# LEDSEQUENCER.net
KiCad netlist of a schematic drawn in Altium Designer
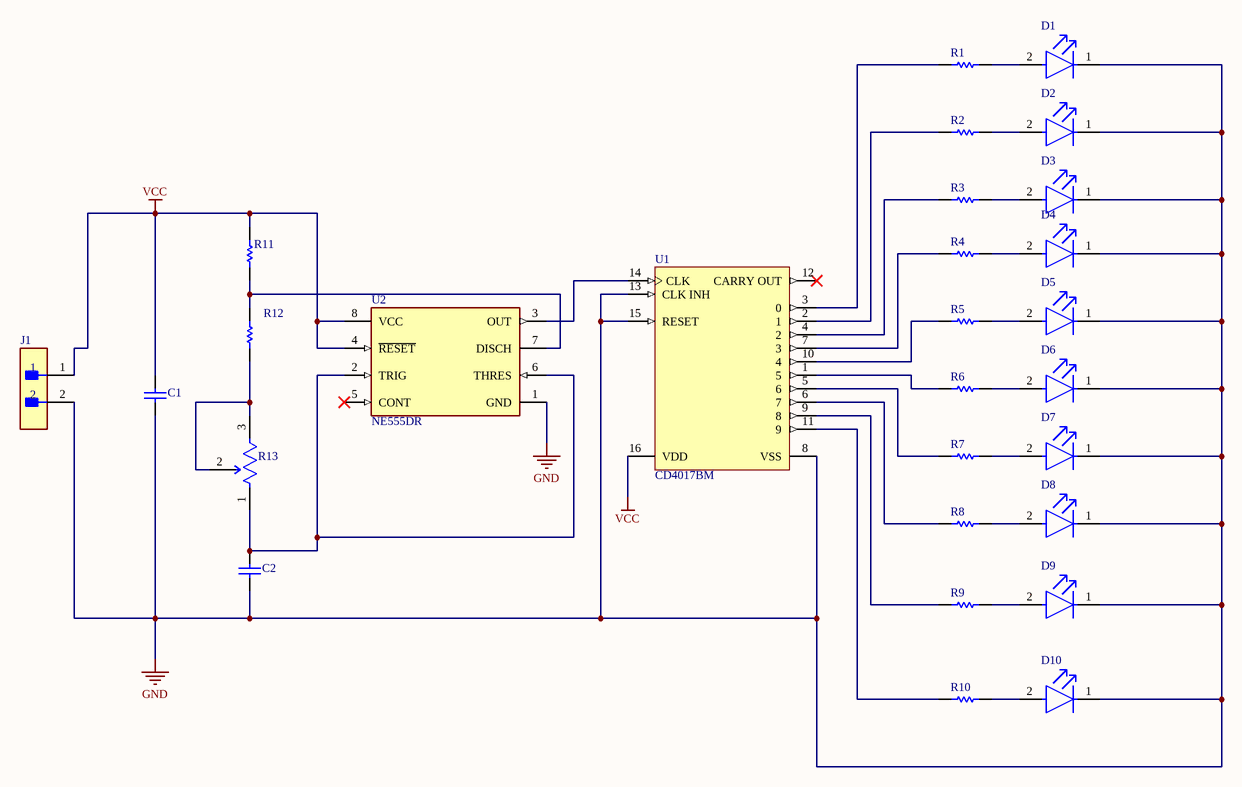
[diagram p0: LEDSEQUENCER.SchDoc]

(export (version "E")
  (design (tool "Eeschema 10.0.6"))
  (components
    (comp (ref "C1")
      (value "1uf")
      (footprint "CAPC2013X135X45LL10T25")
      (fields (field (name "MANUFACTURER") "Murata") (field (name "PART NUMBER") "GRM21BR71H105KA12L"))
      (libsource (lib "Altium Content Vault") (part "CAP"))
    )
    (comp (ref "C2")
      (value "1uf")
      (footprint "CAPC2013X135X45LL10T25")
      (fields (field (name "MANUFACTURER") "Murata") (field (name "PART NUMBER") "GRM21BR71H105KA12L"))
      (libsource (lib "Altium Content Vault") (part "CAP"))
    )
    (comp (ref "D1")
      (value "HLMP-1301")
      (footprint "FP-HLMP-1301-MFG")
      (description "LED RED DIFFUSED T-1 T/H")
      (fields
        (field (name "OCTOPART") "https://octopart.com/hlmp-1301-broadcom-71130345")
        (field (name "MANUFACTURER") "Broadcom")
      )
      (libsource (lib "Altium Content Vault") (part "8706943c75ba83719d021d2fdc84c58"))
    )
    (comp (ref "D2")
      (value "HLMP-1301")
      (footprint "FP-HLMP-1301-MFG")
      (description "LED RED DIFFUSED T-1 T/H")
      (fields
        (field (name "OCTOPART") "https://octopart.com/hlmp-1301-broadcom-71130345")
        (field (name "MANUFACTURER") "Broadcom")
      )
      (libsource (lib "Altium Content Vault") (part "8706943c75ba83719d021d2fdc84c58"))
    )
    (comp (ref "D3")
      (value "HLMP-1301")
      (footprint "FP-HLMP-1301-MFG")
      (description "LED RED DIFFUSED T-1 T/H")
      (fields
        (field (name "OCTOPART") "https://octopart.com/hlmp-1301-broadcom-71130345")
        (field (name "MANUFACTURER") "Broadcom")
      )
      (libsource (lib "Altium Content Vault") (part "8706943c75ba83719d021d2fdc84c58"))
    )
    (comp (ref "D4")
      (value "HLMP-1301")
      (footprint "FP-HLMP-1301-MFG")
      (description "LED RED DIFFUSED T-1 T/H")
      (fields
        (field (name "OCTOPART") "https://octopart.com/hlmp-1301-broadcom-71130345")
        (field (name "MANUFACTURER") "Broadcom")
      )
      (libsource (lib "Altium Content Vault") (part "8706943c75ba83719d021d2fdc84c58"))
    )
    (comp (ref "D5")
      (value "HLMP-1301")
      (footprint "FP-HLMP-1301-MFG")
      (description "LED RED DIFFUSED T-1 T/H")
      (fields
        (field (name "OCTOPART") "https://octopart.com/hlmp-1301-broadcom-71130345")
        (field (name "MANUFACTURER") "Broadcom")
      )
      (libsource (lib "Altium Content Vault") (part "8706943c75ba83719d021d2fdc84c58"))
    )
    (comp (ref "D6")
      (value "HLMP-1301")
      (footprint "FP-HLMP-1301-MFG")
      (description "LED RED DIFFUSED T-1 T/H")
      (fields
        (field (name "OCTOPART") "https://octopart.com/hlmp-1301-broadcom-71130345")
        (field (name "MANUFACTURER") "Broadcom")
      )
      (libsource (lib "Altium Content Vault") (part "8706943c75ba83719d021d2fdc84c58"))
    )
    (comp (ref "D7")
      (value "HLMP-1301")
      (footprint "FP-HLMP-1301-MFG")
      (description "LED RED DIFFUSED T-1 T/H")
      (fields
        (field (name "OCTOPART") "https://octopart.com/hlmp-1301-broadcom-71130345")
        (field (name "MANUFACTURER") "Broadcom")
      )
      (libsource (lib "Altium Content Vault") (part "8706943c75ba83719d021d2fdc84c58"))
    )
    (comp (ref "D8")
      (value "HLMP-1301")
      (footprint "FP-HLMP-1301-MFG")
      (description "LED RED DIFFUSED T-1 T/H")
      (fields
        (field (name "OCTOPART") "https://octopart.com/hlmp-1301-broadcom-71130345")
        (field (name "MANUFACTURER") "Broadcom")
      )
      (libsource (lib "Altium Content Vault") (part "8706943c75ba83719d021d2fdc84c58"))
    )
    (comp (ref "D9")
      (value "HLMP-1301")
      (footprint "FP-HLMP-1301-MFG")
      (description "LED RED DIFFUSED T-1 T/H")
      (fields
        (field (name "OCTOPART") "https://octopart.com/hlmp-1301-broadcom-71130345")
        (field (name "MANUFACTURER") "Broadcom")
      )
      (libsource (lib "Altium Content Vault") (part "8706943c75ba83719d021d2fdc84c58"))
    )
    (comp (ref "D10")
      (value "HLMP-1301")
      (footprint "FP-HLMP-1301-MFG")
      (description "LED RED DIFFUSED T-1 T/H")
      (fields
        (field (name "OCTOPART") "https://octopart.com/hlmp-1301-broadcom-71130345")
        (field (name "MANUFACTURER") "Broadcom")
      )
      (libsource (lib "Altium Content Vault") (part "8706943c75ba83719d021d2fdc84c58"))
    )
    (comp (ref "J1")
      (value "M20-9990246")
      (footprint "FP-M20-9990246-MFG")
      (description "Connector Header Through Hole 2 position 0.100\" (2.54mm)")
      (fields (field (name "OCTOPART") "https://octopart.com/m20-9990246-harwin-2590635"))
      (libsource (lib "Altium Content Vault") (part "3bc925449376181038e59eaffc5286c"))
    )
    (comp (ref "R1")
      (value "1k")
      (footprint "RESC2013X60X35ML10T20")
      (description "Chip Resistor, 1 KOhm, +/- 1%, 125 mW, -55 to 155 degC, 0805 (2012 Metric), RoHS, Tape and Reel")
      (fields (field (name "TOLERANCE") "1%") (field (name "MANUFACTURER") "Yageo"))
      (libsource (lib "Altium Content Vault") (part "RES-2"))
    )
    (comp (ref "R2")
      (value "RC0805FR-071KL")
      (footprint "RESC2013X60X35ML10T20")
      (description "Chip Resistor, 1 KOhm, +/- 1%, 125 mW, -55 to 155 degC, 0805 (2012 Metric), RoHS, Tape and Reel")
      (fields (field (name "TOLERANCE") "1%") (field (name "MANUFACTURER") "Yageo"))
      (libsource (lib "Altium Content Vault") (part "RES-2"))
    )
    (comp (ref "R3")
      (value "RC0805FR-071KL")
      (footprint "RESC2013X60X35ML10T20")
      (description "Chip Resistor, 1 KOhm, +/- 1%, 125 mW, -55 to 155 degC, 0805 (2012 Metric), RoHS, Tape and Reel")
      (fields (field (name "TOLERANCE") "1%") (field (name "MANUFACTURER") "Yageo"))
      (libsource (lib "Altium Content Vault") (part "RES-2"))
    )
    (comp (ref "R4")
      (value "RC0805FR-071KL")
      (footprint "RESC2013X60X35ML10T20")
      (description "Chip Resistor, 1 KOhm, +/- 1%, 125 mW, -55 to 155 degC, 0805 (2012 Metric), RoHS, Tape and Reel")
      (fields (field (name "TOLERANCE") "1%") (field (name "MANUFACTURER") "Yageo"))
      (libsource (lib "Altium Content Vault") (part "RES-2"))
    )
    (comp (ref "R5")
      (value "RC0805FR-071KL")
      (footprint "RESC2013X60X35ML10T20")
      (description "Chip Resistor, 1 KOhm, +/- 1%, 125 mW, -55 to 155 degC, 0805 (2012 Metric), RoHS, Tape and Reel")
      (fields (field (name "TOLERANCE") "1%") (field (name "MANUFACTURER") "Yageo"))
      (libsource (lib "Altium Content Vault") (part "RES-2"))
    )
    (comp (ref "R6")
      (value "RC0805FR-071KL")
      (footprint "RESC2013X60X35ML10T20")
      (description "Chip Resistor, 1 KOhm, +/- 1%, 125 mW, -55 to 155 degC, 0805 (2012 Metric), RoHS, Tape and Reel")
      (fields (field (name "TOLERANCE") "1%") (field (name "MANUFACTURER") "Yageo"))
      (libsource (lib "Altium Content Vault") (part "RES-2"))
    )
    (comp (ref "R7")
      (value "RC0805FR-071KL")
      (footprint "RESC2013X60X35ML10T20")
      (description "Chip Resistor, 1 KOhm, +/- 1%, 125 mW, -55 to 155 degC, 0805 (2012 Metric), RoHS, Tape and Reel")
      (fields (field (name "TOLERANCE") "1%") (field (name "MANUFACTURER") "Yageo"))
      (libsource (lib "Altium Content Vault") (part "RES-2"))
    )
    (comp (ref "R8")
      (value "RC0805FR-071KL")
      (footprint "RESC2013X60X35ML10T20")
      (description "Chip Resistor, 1 KOhm, +/- 1%, 125 mW, -55 to 155 degC, 0805 (2012 Metric), RoHS, Tape and Reel")
      (fields (field (name "TOLERANCE") "1%") (field (name "MANUFACTURER") "Yageo"))
      (libsource (lib "Altium Content Vault") (part "RES-2"))
    )
    (comp (ref "R9")
      (value "RC0805FR-071KL")
      (footprint "RESC2013X60X35ML10T20")
      (description "Chip Resistor, 1 KOhm, +/- 1%, 125 mW, -55 to 155 degC, 0805 (2012 Metric), RoHS, Tape and Reel")
      (fields (field (name "TOLERANCE") "1%") (field (name "MANUFACTURER") "Yageo"))
      (libsource (lib "Altium Content Vault") (part "RES-2"))
    )
    (comp (ref "R10")
      (value "RC0805FR-071KL")
      (footprint "RESC2013X60X35ML10T20")
      (description "Chip Resistor, 1 KOhm, +/- 1%, 125 mW, -55 to 155 degC, 0805 (2012 Metric), RoHS, Tape and Reel")
      (fields (field (name "TOLERANCE") "1%") (field (name "MANUFACTURER") "Yageo"))
      (libsource (lib "Altium Content Vault") (part "RES-2"))
    )
    (comp (ref "R11")
      (value "2.2k")
      (footprint "RESC2013X60X35ML10T20")
      (description "Chip Resistor, 1 KOhm, +/- 1%, 125 mW, -55 to 155 degC, 0805 (2012 Metric), RoHS, Tape and Reel")
      (fields (field (name "TOLERANCE") "1%") (field (name "MANUFACTURER") "Yageo"))
      (libsource (lib "Altium Content Vault") (part "RES-2"))
    )
    (comp (ref "R12")
      (value "10k")
      (footprint "RESC2013X60X35ML10T20")
      (description "Chip Resistor, 1 KOhm, +/- 1%, 125 mW, -55 to 155 degC, 0805 (2012 Metric), RoHS, Tape and Reel")
      (fields (field (name "TOLERANCE") "1%") (field (name "MANUFACTURER") "Yageo"))
      (libsource (lib "Altium Content Vault") (part "RES-2"))
    )
    (comp (ref "R13")
      (value "50k")
      (footprint "FP-3386P-MFG")
      (description "TRIMMER 100K OHM 0.5W PC PIN TOP")
      (fields (field (name "TOLERANCE") "10%"))
      (libsource (lib "Altium Content Vault") (part "13357d81287629c2fd191d242cfa50c"))
    )
    (comp (ref "U1")
      (value "CD4017BM")
      (footprint "D0016A_N")
      (description "CMOS Decade Counter with 10 Decoded Outputs, D0016A, TUBE")
      (fields
        (field (name "GENERIC PART NUMBER") "CD4017B")
        (field (name "MANUFACTURER") "Texas Instruments")
      )
      (libsource (lib "Altium Content Vault") (part "TI-CD4017B-16"))
    )
    (comp (ref "U2")
      (value "NE555DR")
      (footprint "FP-D0008A-IPC_A")
      (description "IC OSC SGL TIMER 100KHZ 8-SOIC")
      (libsource (lib "Altium Content Vault") (part "a29bba90211dec1890110b94dad7d53"))
    )
  )
  (nets
    (net (code "1") (name "GND") (class "Default")
      (node (ref "C1") (pin "1") (pinfunction "1_1") (pintype "passive"))
      (node (ref "C2") (pin "1") (pinfunction "1_1") (pintype "passive"))
      (node (ref "D1") (pin "1") (pinfunction "C_1") (pintype "passive"))
      (node (ref "D10") (pin "1") (pinfunction "C_1") (pintype "passive"))
      (node (ref "D2") (pin "1") (pinfunction "C_1") (pintype "passive"))
      (node (ref "D3") (pin "1") (pinfunction "C_1") (pintype "passive"))
      (node (ref "D4") (pin "1") (pinfunction "C_1") (pintype "passive"))
      (node (ref "D5") (pin "1") (pinfunction "C_1") (pintype "passive"))
      (node (ref "D6") (pin "1") (pinfunction "C_1") (pintype "passive"))
      (node (ref "D7") (pin "1") (pinfunction "C_1") (pintype "passive"))
      (node (ref "D8") (pin "1") (pinfunction "C_1") (pintype "passive"))
      (node (ref "D9") (pin "1") (pinfunction "C_1") (pintype "passive"))
      (node (ref "J1") (pin "2") (pinfunction "2_2") (pintype "passive"))
      (node (ref "U1") (pin "13") (pinfunction "CLK_INH_13") (pintype "input"))
      (node (ref "U1") (pin "15") (pinfunction "RESET_15") (pintype "input"))
      (node (ref "U1") (pin "8") (pinfunction "VSS_8") (pintype "power_in"))
      (node (ref "U2") (pin "1") (pinfunction "GND_1") (pintype "power_in"))
    )
    (net (code "2") (name "Net-(D1-A)") (class "Default")
      (node (ref "D1") (pin "2") (pinfunction "A_2") (pintype "passive"))
      (node (ref "R1") (pin "2") (pinfunction "2_2") (pintype "passive"))
    )
    (net (code "3") (name "Net-(D2-A)") (class "Default")
      (node (ref "D2") (pin "2") (pinfunction "A_2") (pintype "passive"))
      (node (ref "R2") (pin "2") (pinfunction "2_2") (pintype "passive"))
    )
    (net (code "4") (name "Net-(D3-A)") (class "Default")
      (node (ref "D3") (pin "2") (pinfunction "A_2") (pintype "passive"))
      (node (ref "R3") (pin "2") (pinfunction "2_2") (pintype "passive"))
    )
    (net (code "5") (name "Net-(D4-A)") (class "Default")
      (node (ref "D4") (pin "2") (pinfunction "A_2") (pintype "passive"))
      (node (ref "R4") (pin "2") (pinfunction "2_2") (pintype "passive"))
    )
    (net (code "6") (name "Net-(D5-A)") (class "Default")
      (node (ref "D5") (pin "2") (pinfunction "A_2") (pintype "passive"))
      (node (ref "R5") (pin "2") (pinfunction "2_2") (pintype "passive"))
    )
    (net (code "7") (name "Net-(D6-A)") (class "Default")
      (node (ref "D6") (pin "2") (pinfunction "A_2") (pintype "passive"))
      (node (ref "R6") (pin "2") (pinfunction "2_2") (pintype "passive"))
    )
    (net (code "8") (name "Net-(D7-A)") (class "Default")
      (node (ref "D7") (pin "2") (pinfunction "A_2") (pintype "passive"))
      (node (ref "R7") (pin "2") (pinfunction "2_2") (pintype "passive"))
    )
    (net (code "9") (name "Net-(D8-A)") (class "Default")
      (node (ref "D8") (pin "2") (pinfunction "A_2") (pintype "passive"))
      (node (ref "R8") (pin "2") (pinfunction "2_2") (pintype "passive"))
    )
    (net (code "10") (name "Net-(D9-A)") (class "Default")
      (node (ref "D9") (pin "2") (pinfunction "A_2") (pintype "passive"))
      (node (ref "R9") (pin "2") (pinfunction "2_2") (pintype "passive"))
    )
    (net (code "11") (name "Net-(D10-A)") (class "Default")
      (node (ref "D10") (pin "2") (pinfunction "A_2") (pintype "passive"))
      (node (ref "R10") (pin "2") (pinfunction "2_2") (pintype "passive"))
    )
    (net (code "12") (name "Net-(R13-CCW)") (class "Default")
      (node (ref "C2") (pin "2") (pinfunction "2_2") (pintype "passive"))
      (node (ref "R13") (pin "1") (pinfunction "CCW_1") (pintype "passive"))
      (node (ref "U2") (pin "2") (pinfunction "TRIG_2") (pintype "input"))
      (node (ref "U2") (pin "6") (pinfunction "THRES_6") (pintype "input"))
    )
    (net (code "13") (name "Net-(R13-CW)") (class "Default")
      (node (ref "R12") (pin "1") (pinfunction "1_1") (pintype "passive"))
      (node (ref "R13") (pin "2") (pinfunction "WIPER_2") (pintype "passive"))
      (node (ref "R13") (pin "3") (pinfunction "CW_3") (pintype "passive"))
    )
    (net (code "14") (name "Net-(U1-0)") (class "Default")
      (node (ref "R1") (pin "1") (pinfunction "1_1") (pintype "passive"))
      (node (ref "U1") (pin "3") (pinfunction "0_3") (pintype "output"))
    )
    (net (code "15") (name "Net-(U1-1)") (class "Default")
      (node (ref "R2") (pin "1") (pinfunction "1_1") (pintype "passive"))
      (node (ref "U1") (pin "2") (pinfunction "1_2") (pintype "output"))
    )
    (net (code "16") (name "Net-(U1-2)") (class "Default")
      (node (ref "R3") (pin "1") (pinfunction "1_1") (pintype "passive"))
      (node (ref "U1") (pin "4") (pinfunction "2_4") (pintype "output"))
    )
    (net (code "17") (name "Net-(U1-3)") (class "Default")
      (node (ref "R4") (pin "1") (pinfunction "1_1") (pintype "passive"))
      (node (ref "U1") (pin "7") (pinfunction "3_7") (pintype "output"))
    )
    (net (code "18") (name "Net-(U1-4)") (class "Default")
      (node (ref "R5") (pin "1") (pinfunction "1_1") (pintype "passive"))
      (node (ref "U1") (pin "10") (pinfunction "4_10") (pintype "output"))
    )
    (net (code "19") (name "Net-(U1-5)") (class "Default")
      (node (ref "R6") (pin "1") (pinfunction "1_1") (pintype "passive"))
      (node (ref "U1") (pin "1") (pinfunction "5_1") (pintype "output"))
    )
    (net (code "20") (name "Net-(U1-6)") (class "Default")
      (node (ref "R7") (pin "1") (pinfunction "1_1") (pintype "passive"))
      (node (ref "U1") (pin "5") (pinfunction "6_5") (pintype "output"))
    )
    (net (code "21") (name "Net-(U1-7)") (class "Default")
      (node (ref "R8") (pin "1") (pinfunction "1_1") (pintype "passive"))
      (node (ref "U1") (pin "6") (pinfunction "7_6") (pintype "output"))
    )
    (net (code "22") (name "Net-(U1-8)") (class "Default")
      (node (ref "R9") (pin "1") (pinfunction "1_1") (pintype "passive"))
      (node (ref "U1") (pin "9") (pinfunction "8_9") (pintype "output"))
    )
    (net (code "23") (name "Net-(U1-9)") (class "Default")
      (node (ref "R10") (pin "1") (pinfunction "1_1") (pintype "passive"))
      (node (ref "U1") (pin "11") (pinfunction "9_11") (pintype "output"))
    )
    (net (code "24") (name "Net-(U1-CLK)") (class "Default")
      (node (ref "U1") (pin "14") (pinfunction "CLK_14") (pintype "input"))
      (node (ref "U2") (pin "3") (pinfunction "OUT_3") (pintype "output"))
    )
    (net (code "25") (name "Net-(U2-DISCH)") (class "Default")
      (node (ref "R11") (pin "1") (pinfunction "1_1") (pintype "passive"))
      (node (ref "R12") (pin "2") (pinfunction "2_2") (pintype "passive"))
      (node (ref "U2") (pin "7") (pinfunction "DISCH_7") (pintype "open_collector"))
    )
    (net (code "26") (name "VCC") (class "Default")
      (node (ref "C1") (pin "2") (pinfunction "2_2") (pintype "passive"))
      (node (ref "J1") (pin "1") (pinfunction "1_1") (pintype "passive"))
      (node (ref "R11") (pin "2") (pinfunction "2_2") (pintype "passive"))
      (node (ref "U1") (pin "16") (pinfunction "VDD_16") (pintype "power_in"))
      (node (ref "U2") (pin "4") (pinfunction "~{RESET}_4") (pintype "input"))
      (node (ref "U2") (pin "8") (pinfunction "VCC_8") (pintype "power_in"))
    )
    (net (code "27") (name "unconnected-(U1-CARRY_OUT-Pad12)") (class "Default")
      (node (ref "U1") (pin "12") (pinfunction "CARRY_OUT_12") (pintype "output+no_connect"))
    )
    (net (code "28") (name "unconnected-(U2-CONT-Pad5)") (class "Default")
      (node (ref "U2") (pin "5") (pinfunction "CONT_5") (pintype "input+no_connect"))
    )
  )
)
